# blinkyboard.net
KiCad netlist of a schematic drawn in EAGLE
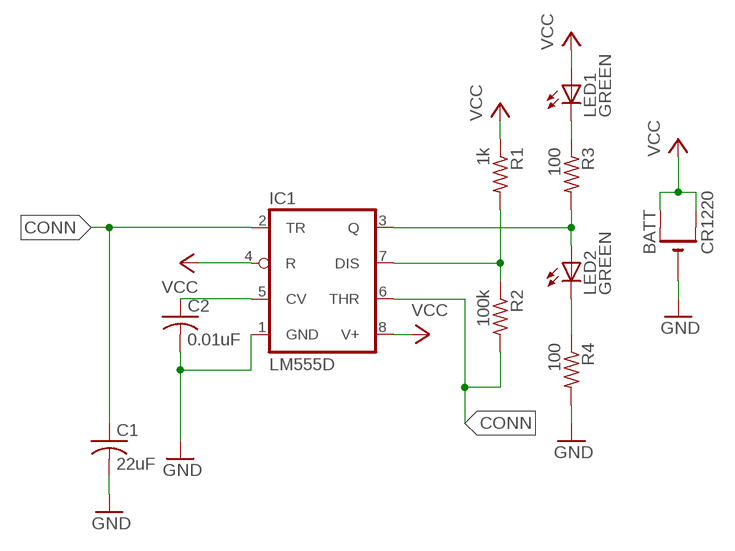
[diagram p0: schematic, sheet 1]

(export (version "E")
  (design (tool "Eeschema 10.0.6"))
  (components
    (comp (ref "BATT")
      (value "CR1220")
      (footprint "eagle-import:CR1220-SMD")
      (fields (field (name "MF") "KEYSTONE") (field (name "MPN") "3001"))
      (libsource (lib "eagle-import") (part "CR1220SMT"))
    )
    (comp (ref "C1")
      (value "22uF")
      (footprint "eagle-import:C0805")
      (fields (field (name "MF") "KEMET") (field (name "MPN") "C0805C226M9PACTU"))
      (libsource (lib "eagle-import") (part "C-USC0805"))
    )
    (comp (ref "C2")
      (value "0.01uF")
      (footprint "eagle-import:C0805")
      (fields (field (name "MF") "AVX") (field (name "MPN") "04023D103KAT2A"))
      (libsource (lib "eagle-import") (part "C-USC0805"))
    )
    (comp (ref "IC1")
      (value "LM555D")
      (footprint "eagle-import:SO08")
      (fields (field (name "MF") "TEXAS INSTRUMENTS") (field (name "MPN") "TLC555CDR"))
      (libsource (lib "eagle-import") (part "555DLM"))
    )
    (comp (ref "LED1")
      (value "GREEN")
      (footprint "eagle-import:CHIPLED_0805")
      (fields (field (name "MF") "DIALIGHT") (field (name "MPN") "5988170107F"))
      (libsource (lib "eagle-import") (part "LEDCHIPLED_0805"))
    )
    (comp (ref "LED2")
      (value "GREEN")
      (footprint "eagle-import:CHIPLED_0805")
      (fields (field (name "MF") "DIALIGHT") (field (name "MPN") "5988170107F"))
      (libsource (lib "eagle-import") (part "LEDCHIPLED_0805"))
    )
    (comp (ref "R1")
      (value "1k")
      (footprint "eagle-import:R0805")
      (fields (field (name "MF") "VISHAY DRALORIC") (field (name "MPN") "CRCW08051K00FKEA"))
      (libsource (lib "eagle-import") (part "R-US_R0805"))
    )
    (comp (ref "R2")
      (value "100k")
      (footprint "eagle-import:R0805")
      (fields (field (name "MF") "VISHAY DRALORIC") (field (name "MPN") "CRCW0805100KFKEA"))
      (libsource (lib "eagle-import") (part "R-US_R0805"))
    )
    (comp (ref "R3")
      (value "100")
      (footprint "eagle-import:R0805")
      (fields (field (name "MF") "BOURNS") (field (name "MPN") "CR0805-JW-101ELF"))
      (libsource (lib "eagle-import") (part "R-US_R0805"))
    )
    (comp (ref "R4")
      (value "100")
      (footprint "eagle-import:R0805")
      (fields (field (name "MF") "BOURNS") (field (name "MPN") "CR0805-JW-101ELF"))
      (libsource (lib "eagle-import") (part "R-US_R0805"))
    )
  )
  (nets
    (net (code "1") (name "CONN") (class "Default")
      (node (ref "C1") (pin "1") (pinfunction "1_1") (pintype "passive"))
      (node (ref "IC1") (pin "2") (pinfunction "TR_2") (pintype "input"))
      (node (ref "IC1") (pin "6") (pinfunction "THR_6") (pintype "input"))
      (node (ref "R2") (pin "2") (pinfunction "2_2") (pintype "passive"))
    )
    (net (code "2") (name "GND") (class "Default")
      (node (ref "BATT") (pin "-") (pinfunction "-_-") (pintype "passive"))
      (node (ref "C1") (pin "2") (pinfunction "2_2") (pintype "passive"))
      (node (ref "C2") (pin "2") (pinfunction "2_2") (pintype "passive"))
      (node (ref "IC1") (pin "1") (pinfunction "GND_1") (pintype "power_in"))
      (node (ref "R4") (pin "2") (pinfunction "2_2") (pintype "passive"))
    )
    (net (code "3") (name "Net-(IC1-CV)") (class "Default")
      (node (ref "C2") (pin "1") (pinfunction "1_1") (pintype "passive"))
      (node (ref "IC1") (pin "5") (pinfunction "CV_5") (pintype "input"))
    )
    (net (code "4") (name "Net-(IC1-DIS)") (class "Default")
      (node (ref "IC1") (pin "7") (pinfunction "DIS_7") (pintype "input"))
      (node (ref "R1") (pin "2") (pinfunction "2_2") (pintype "passive"))
      (node (ref "R2") (pin "1") (pinfunction "1_1") (pintype "passive"))
    )
    (net (code "5") (name "Net-(IC1-Q)") (class "Default")
      (node (ref "IC1") (pin "3") (pinfunction "Q_3") (pintype "output"))
      (node (ref "LED2") (pin "A") (pinfunction "A_A") (pintype "passive"))
      (node (ref "R3") (pin "2") (pinfunction "2_2") (pintype "passive"))
    )
    (net (code "6") (name "Net-(LED1-PadC)") (class "Default")
      (node (ref "LED1") (pin "C") (pinfunction "C_C") (pintype "passive"))
      (node (ref "R3") (pin "1") (pinfunction "1_1") (pintype "passive"))
    )
    (net (code "7") (name "Net-(LED2-PadC)") (class "Default")
      (node (ref "LED2") (pin "C") (pinfunction "C_C") (pintype "passive"))
      (node (ref "R4") (pin "1") (pinfunction "1_1") (pintype "passive"))
    )
    (net (code "8") (name "VCC") (class "Default")
      (node (ref "BATT") (pin "+$1") (pinfunction "+_+$1") (pintype "passive"))
      (node (ref "BATT") (pin "+$2") (pinfunction "+1_+$2") (pintype "passive"))
      (node (ref "IC1") (pin "4") (pinfunction "R_4") (pintype "input"))
      (node (ref "IC1") (pin "8") (pinfunction "V+_8") (pintype "power_in"))
      (node (ref "LED1") (pin "A") (pinfunction "A_A") (pintype "passive"))
      (node (ref "R1") (pin "1") (pinfunction "1_1") (pintype "passive"))
    )
  )
)
